# step_motor.net
KiCad netlist of a schematic drawn in EAGLE
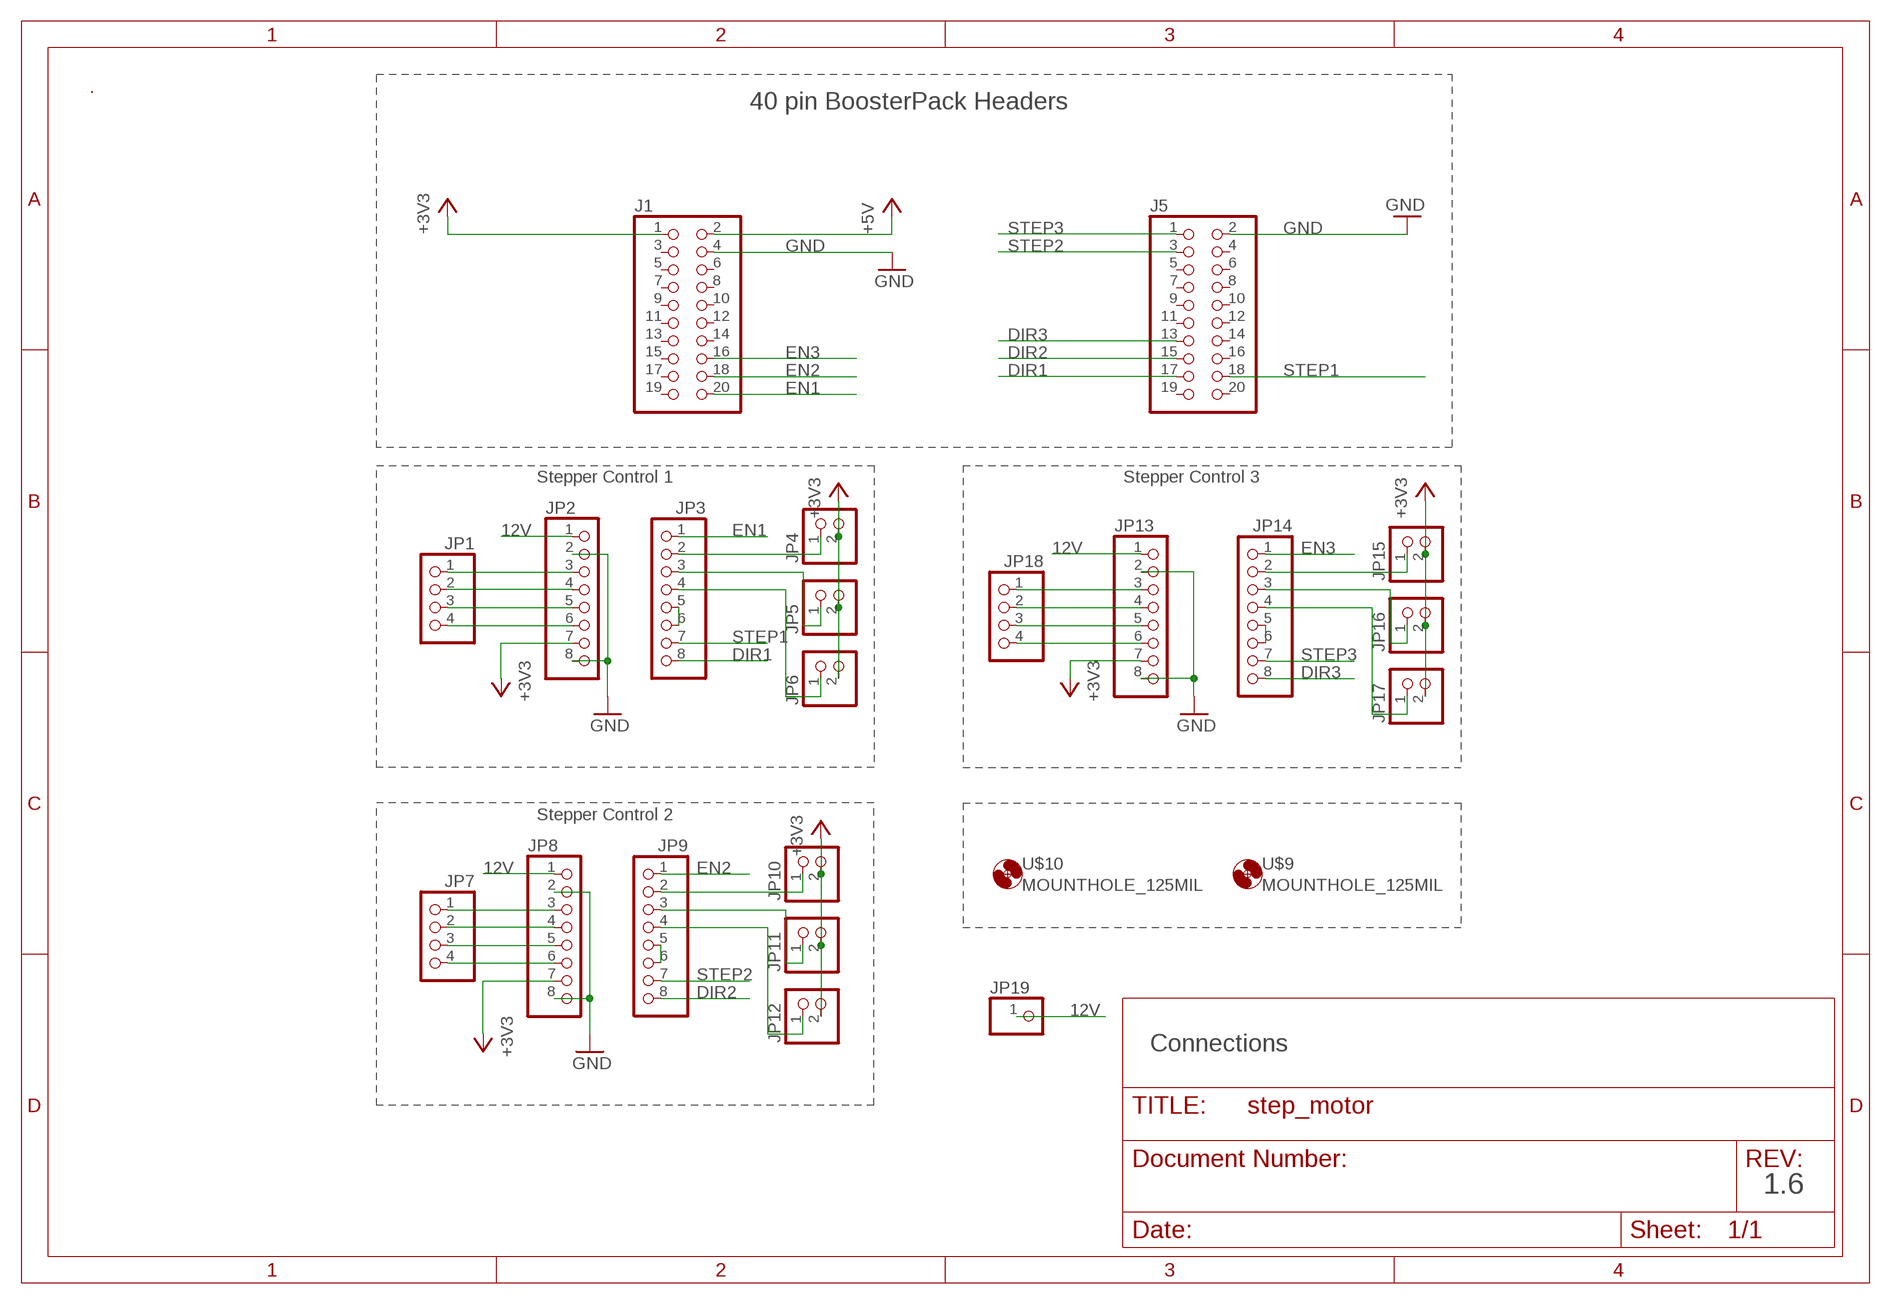
[diagram p0: schematic, sheet 1]

(export (version "E")
  (design (tool "Eeschema 10.0.6"))
  (components
    (comp (ref "J1")
      (value "PINHD-2X10")
      (footprint "eagle-import:2X10")
      (libsource (lib "eagle-import") (part "PINHD-2X10"))
    )
    (comp (ref "J5")
      (value "PINHD-2X10")
      (footprint "eagle-import:2X10")
      (libsource (lib "eagle-import") (part "PINHD-2X10"))
    )
    (comp (ref "JP1")
      (value "PINHD-1X4")
      (footprint "eagle-import:1X04")
      (libsource (lib "eagle-import") (part "PINHD-1X4"))
    )
    (comp (ref "JP2")
      (value "PINHD-1X8")
      (footprint "eagle-import:1X08")
      (libsource (lib "eagle-import") (part "PINHD-1X8"))
    )
    (comp (ref "JP3")
      (value "PINHD-1X8")
      (footprint "eagle-import:1X08")
      (libsource (lib "eagle-import") (part "PINHD-1X8"))
    )
    (comp (ref "JP4")
      (value "PINHD-1X2")
      (footprint "eagle-import:1X02")
      (libsource (lib "eagle-import") (part "PINHD-1X2"))
    )
    (comp (ref "JP5")
      (value "PINHD-1X2")
      (footprint "eagle-import:1X02")
      (libsource (lib "eagle-import") (part "PINHD-1X2"))
    )
    (comp (ref "JP6")
      (value "PINHD-1X2")
      (footprint "eagle-import:1X02")
      (libsource (lib "eagle-import") (part "PINHD-1X2"))
    )
    (comp (ref "JP7")
      (value "PINHD-1X4")
      (footprint "eagle-import:1X04")
      (libsource (lib "eagle-import") (part "PINHD-1X4"))
    )
    (comp (ref "JP8")
      (value "PINHD-1X8")
      (footprint "eagle-import:1X08")
      (libsource (lib "eagle-import") (part "PINHD-1X8"))
    )
    (comp (ref "JP9")
      (value "PINHD-1X8")
      (footprint "eagle-import:1X08")
      (libsource (lib "eagle-import") (part "PINHD-1X8"))
    )
    (comp (ref "JP10")
      (value "PINHD-1X2")
      (footprint "eagle-import:1X02")
      (libsource (lib "eagle-import") (part "PINHD-1X2"))
    )
    (comp (ref "JP11")
      (value "PINHD-1X2")
      (footprint "eagle-import:1X02")
      (libsource (lib "eagle-import") (part "PINHD-1X2"))
    )
    (comp (ref "JP12")
      (value "PINHD-1X2")
      (footprint "eagle-import:1X02")
      (libsource (lib "eagle-import") (part "PINHD-1X2"))
    )
    (comp (ref "JP13")
      (value "PINHD-1X8")
      (footprint "eagle-import:1X08")
      (libsource (lib "eagle-import") (part "PINHD-1X8"))
    )
    (comp (ref "JP14")
      (value "PINHD-1X8")
      (footprint "eagle-import:1X08")
      (libsource (lib "eagle-import") (part "PINHD-1X8"))
    )
    (comp (ref "JP15")
      (value "PINHD-1X2")
      (footprint "eagle-import:1X02")
      (libsource (lib "eagle-import") (part "PINHD-1X2"))
    )
    (comp (ref "JP16")
      (value "PINHD-1X2")
      (footprint "eagle-import:1X02")
      (libsource (lib "eagle-import") (part "PINHD-1X2"))
    )
    (comp (ref "JP17")
      (value "PINHD-1X2")
      (footprint "eagle-import:1X02")
      (libsource (lib "eagle-import") (part "PINHD-1X2"))
    )
    (comp (ref "JP18")
      (value "PINHD-1X4")
      (footprint "eagle-import:1X04")
      (libsource (lib "eagle-import") (part "PINHD-1X4"))
    )
    (comp (ref "JP19")
      (value "PINHD-1X1")
      (footprint "eagle-import:1X01")
      (libsource (lib "eagle-import") (part "PINHD-1X1"))
    )
    (comp (ref "U$4")
      (value "MS_TM")
      (footprint "eagle-import:MS_TM")
      (libsource (lib "eagle-import") (part "MS_TM"))
    )
    (comp (ref "U$9")
      (value "MOUNTHOLE_125MIL")
      (footprint "eagle-import:MOUNTHOLE_125MIL")
      (libsource (lib "eagle-import") (part "MOUNTHOLE_125MIL"))
    )
    (comp (ref "U$10")
      (value "MOUNTHOLE_125MIL")
      (footprint "eagle-import:MOUNTHOLE_125MIL")
      (libsource (lib "eagle-import") (part "MOUNTHOLE_125MIL"))
    )
  )
  (nets
    (net (code "1") (name "+3V3") (class "Default")
      (node (ref "J1") (pin "1") (pinfunction "1_1") (pintype "passive"))
      (node (ref "JP10") (pin "2") (pinfunction "2_2") (pintype "passive"))
      (node (ref "JP11") (pin "2") (pinfunction "2_2") (pintype "passive"))
      (node (ref "JP12") (pin "2") (pinfunction "2_2") (pintype "passive"))
      (node (ref "JP13") (pin "7") (pinfunction "7_7") (pintype "passive"))
      (node (ref "JP15") (pin "2") (pinfunction "2_2") (pintype "passive"))
      (node (ref "JP16") (pin "2") (pinfunction "2_2") (pintype "passive"))
      (node (ref "JP17") (pin "2") (pinfunction "2_2") (pintype "passive"))
      (node (ref "JP2") (pin "7") (pinfunction "7_7") (pintype "passive"))
      (node (ref "JP4") (pin "2") (pinfunction "2_2") (pintype "passive"))
      (node (ref "JP5") (pin "2") (pinfunction "2_2") (pintype "passive"))
      (node (ref "JP6") (pin "2") (pinfunction "2_2") (pintype "passive"))
      (node (ref "JP8") (pin "7") (pinfunction "7_7") (pintype "passive"))
    )
    (net (code "2") (name "+5V") (class "Default")
      (node (ref "J1") (pin "2") (pinfunction "2_2") (pintype "passive"))
    )
    (net (code "3") (name "/12V") (class "Default")
      (node (ref "JP13") (pin "1") (pinfunction "1_1") (pintype "passive"))
      (node (ref "JP19") (pin "1") (pinfunction "1_1") (pintype "passive"))
      (node (ref "JP2") (pin "1") (pinfunction "1_1") (pintype "passive"))
      (node (ref "JP8") (pin "1") (pinfunction "1_1") (pintype "passive"))
    )
    (net (code "4") (name "/DIR1") (class "Default")
      (node (ref "J5") (pin "17") (pinfunction "17_17") (pintype "passive"))
      (node (ref "JP3") (pin "8") (pinfunction "8_8") (pintype "passive"))
    )
    (net (code "5") (name "/DIR2") (class "Default")
      (node (ref "J5") (pin "15") (pinfunction "15_15") (pintype "passive"))
      (node (ref "JP9") (pin "8") (pinfunction "8_8") (pintype "passive"))
    )
    (net (code "6") (name "/DIR3") (class "Default")
      (node (ref "J5") (pin "13") (pinfunction "13_13") (pintype "passive"))
      (node (ref "JP14") (pin "8") (pinfunction "8_8") (pintype "passive"))
    )
    (net (code "7") (name "/EN1") (class "Default")
      (node (ref "J1") (pin "20") (pinfunction "20_20") (pintype "passive"))
      (node (ref "JP3") (pin "1") (pinfunction "1_1") (pintype "passive"))
    )
    (net (code "8") (name "/EN2") (class "Default")
      (node (ref "J1") (pin "18") (pinfunction "18_18") (pintype "passive"))
      (node (ref "JP9") (pin "1") (pinfunction "1_1") (pintype "passive"))
    )
    (net (code "9") (name "/EN3") (class "Default")
      (node (ref "J1") (pin "16") (pinfunction "16_16") (pintype "passive"))
      (node (ref "JP14") (pin "1") (pinfunction "1_1") (pintype "passive"))
    )
    (net (code "10") (name "/STEP1") (class "Default")
      (node (ref "J5") (pin "18") (pinfunction "18_18") (pintype "passive"))
      (node (ref "JP3") (pin "7") (pinfunction "7_7") (pintype "passive"))
    )
    (net (code "11") (name "/STEP2") (class "Default")
      (node (ref "J5") (pin "3") (pinfunction "3_3") (pintype "passive"))
      (node (ref "JP9") (pin "7") (pinfunction "7_7") (pintype "passive"))
    )
    (net (code "12") (name "/STEP3") (class "Default")
      (node (ref "J5") (pin "1") (pinfunction "1_1") (pintype "passive"))
      (node (ref "JP14") (pin "7") (pinfunction "7_7") (pintype "passive"))
    )
    (net (code "13") (name "GND") (class "Default")
      (node (ref "J1") (pin "4") (pinfunction "4_4") (pintype "passive"))
      (node (ref "J5") (pin "2") (pinfunction "2_2") (pintype "passive"))
      (node (ref "JP13") (pin "2") (pinfunction "2_2") (pintype "passive"))
      (node (ref "JP13") (pin "8") (pinfunction "8_8") (pintype "passive"))
      (node (ref "JP2") (pin "2") (pinfunction "2_2") (pintype "passive"))
      (node (ref "JP2") (pin "8") (pinfunction "8_8") (pintype "passive"))
      (node (ref "JP8") (pin "2") (pinfunction "2_2") (pintype "passive"))
      (node (ref "JP8") (pin "8") (pinfunction "8_8") (pintype "passive"))
    )
    (net (code "14") (name "Net-(JP1-Pad1)") (class "Default")
      (node (ref "JP1") (pin "1") (pinfunction "1_1") (pintype "passive"))
      (node (ref "JP2") (pin "3") (pinfunction "3_3") (pintype "passive"))
    )
    (net (code "15") (name "Net-(JP1-Pad2)") (class "Default")
      (node (ref "JP1") (pin "2") (pinfunction "2_2") (pintype "passive"))
      (node (ref "JP2") (pin "4") (pinfunction "4_4") (pintype "passive"))
    )
    (net (code "16") (name "Net-(JP1-Pad3)") (class "Default")
      (node (ref "JP1") (pin "3") (pinfunction "3_3") (pintype "passive"))
      (node (ref "JP2") (pin "5") (pinfunction "5_5") (pintype "passive"))
    )
    (net (code "17") (name "Net-(JP1-Pad4)") (class "Default")
      (node (ref "JP1") (pin "4") (pinfunction "4_4") (pintype "passive"))
      (node (ref "JP2") (pin "6") (pinfunction "6_6") (pintype "passive"))
    )
    (net (code "18") (name "Net-(JP3-Pad2)") (class "Default")
      (node (ref "JP3") (pin "2") (pinfunction "2_2") (pintype "passive"))
      (node (ref "JP4") (pin "1") (pinfunction "1_1") (pintype "passive"))
    )
    (net (code "19") (name "Net-(JP3-Pad3)") (class "Default")
      (node (ref "JP3") (pin "3") (pinfunction "3_3") (pintype "passive"))
      (node (ref "JP5") (pin "1") (pinfunction "1_1") (pintype "passive"))
    )
    (net (code "20") (name "Net-(JP3-Pad4)") (class "Default")
      (node (ref "JP3") (pin "4") (pinfunction "4_4") (pintype "passive"))
      (node (ref "JP6") (pin "1") (pinfunction "1_1") (pintype "passive"))
    )
    (net (code "21") (name "Net-(JP3-Pad5)") (class "Default")
      (node (ref "JP3") (pin "5") (pinfunction "5_5") (pintype "passive"))
      (node (ref "JP3") (pin "6") (pinfunction "6_6") (pintype "passive"))
    )
    (net (code "22") (name "Net-(JP7-Pad1)") (class "Default")
      (node (ref "JP7") (pin "1") (pinfunction "1_1") (pintype "passive"))
      (node (ref "JP8") (pin "3") (pinfunction "3_3") (pintype "passive"))
    )
    (net (code "23") (name "Net-(JP7-Pad2)") (class "Default")
      (node (ref "JP7") (pin "2") (pinfunction "2_2") (pintype "passive"))
      (node (ref "JP8") (pin "4") (pinfunction "4_4") (pintype "passive"))
    )
    (net (code "24") (name "Net-(JP7-Pad3)") (class "Default")
      (node (ref "JP7") (pin "3") (pinfunction "3_3") (pintype "passive"))
      (node (ref "JP8") (pin "5") (pinfunction "5_5") (pintype "passive"))
    )
    (net (code "25") (name "Net-(JP7-Pad4)") (class "Default")
      (node (ref "JP7") (pin "4") (pinfunction "4_4") (pintype "passive"))
      (node (ref "JP8") (pin "6") (pinfunction "6_6") (pintype "passive"))
    )
    (net (code "26") (name "Net-(JP9-Pad5)") (class "Default")
      (node (ref "JP9") (pin "5") (pinfunction "5_5") (pintype "passive"))
      (node (ref "JP9") (pin "6") (pinfunction "6_6") (pintype "passive"))
    )
    (net (code "27") (name "Net-(JP10-Pad1)") (class "Default")
      (node (ref "JP10") (pin "1") (pinfunction "1_1") (pintype "passive"))
      (node (ref "JP9") (pin "2") (pinfunction "2_2") (pintype "passive"))
    )
    (net (code "28") (name "Net-(JP11-Pad1)") (class "Default")
      (node (ref "JP11") (pin "1") (pinfunction "1_1") (pintype "passive"))
      (node (ref "JP9") (pin "3") (pinfunction "3_3") (pintype "passive"))
    )
    (net (code "29") (name "Net-(JP12-Pad1)") (class "Default")
      (node (ref "JP12") (pin "1") (pinfunction "1_1") (pintype "passive"))
      (node (ref "JP9") (pin "4") (pinfunction "4_4") (pintype "passive"))
    )
    (net (code "30") (name "Net-(JP13-Pad3)") (class "Default")
      (node (ref "JP13") (pin "3") (pinfunction "3_3") (pintype "passive"))
      (node (ref "JP18") (pin "1") (pinfunction "1_1") (pintype "passive"))
    )
    (net (code "31") (name "Net-(JP13-Pad4)") (class "Default")
      (node (ref "JP13") (pin "4") (pinfunction "4_4") (pintype "passive"))
      (node (ref "JP18") (pin "2") (pinfunction "2_2") (pintype "passive"))
    )
    (net (code "32") (name "Net-(JP13-Pad5)") (class "Default")
      (node (ref "JP13") (pin "5") (pinfunction "5_5") (pintype "passive"))
      (node (ref "JP18") (pin "3") (pinfunction "3_3") (pintype "passive"))
    )
    (net (code "33") (name "Net-(JP13-Pad6)") (class "Default")
      (node (ref "JP13") (pin "6") (pinfunction "6_6") (pintype "passive"))
      (node (ref "JP18") (pin "4") (pinfunction "4_4") (pintype "passive"))
    )
    (net (code "34") (name "Net-(JP14-Pad2)") (class "Default")
      (node (ref "JP14") (pin "2") (pinfunction "2_2") (pintype "passive"))
      (node (ref "JP15") (pin "1") (pinfunction "1_1") (pintype "passive"))
    )
    (net (code "35") (name "Net-(JP14-Pad3)") (class "Default")
      (node (ref "JP14") (pin "3") (pinfunction "3_3") (pintype "passive"))
      (node (ref "JP16") (pin "1") (pinfunction "1_1") (pintype "passive"))
    )
    (net (code "36") (name "Net-(JP14-Pad4)") (class "Default")
      (node (ref "JP14") (pin "4") (pinfunction "4_4") (pintype "passive"))
      (node (ref "JP17") (pin "1") (pinfunction "1_1") (pintype "passive"))
    )
    (net (code "37") (name "Net-(JP14-Pad5)") (class "Default")
      (node (ref "JP14") (pin "5") (pinfunction "5_5") (pintype "passive"))
      (node (ref "JP14") (pin "6") (pinfunction "6_6") (pintype "passive"))
    )
    (net (code "38") (name "unconnected-(J1-Pad3)") (class "Default")
      (node (ref "J1") (pin "3") (pinfunction "3_3") (pintype "passive"))
    )
    (net (code "39") (name "unconnected-(J1-Pad5)") (class "Default")
      (node (ref "J1") (pin "5") (pinfunction "5_5") (pintype "passive"))
    )
    (net (code "40") (name "unconnected-(J1-Pad6)") (class "Default")
      (node (ref "J1") (pin "6") (pinfunction "6_6") (pintype "passive"))
    )
    (net (code "41") (name "unconnected-(J1-Pad7)") (class "Default")
      (node (ref "J1") (pin "7") (pinfunction "7_7") (pintype "passive"))
    )
    (net (code "42") (name "unconnected-(J1-Pad8)") (class "Default")
      (node (ref "J1") (pin "8") (pinfunction "8_8") (pintype "passive"))
    )
    (net (code "43") (name "unconnected-(J1-Pad9)") (class "Default")
      (node (ref "J1") (pin "9") (pinfunction "9_9") (pintype "passive"))
    )
    (net (code "44") (name "unconnected-(J1-Pad10)") (class "Default")
      (node (ref "J1") (pin "10") (pinfunction "10_10") (pintype "passive"))
    )
    (net (code "45") (name "unconnected-(J1-Pad11)") (class "Default")
      (node (ref "J1") (pin "11") (pinfunction "11_11") (pintype "passive"))
    )
    (net (code "46") (name "unconnected-(J1-Pad12)") (class "Default")
      (node (ref "J1") (pin "12") (pinfunction "12_12") (pintype "passive"))
    )
    (net (code "47") (name "unconnected-(J1-Pad13)") (class "Default")
      (node (ref "J1") (pin "13") (pinfunction "13_13") (pintype "passive"))
    )
    (net (code "48") (name "unconnected-(J1-Pad14)") (class "Default")
      (node (ref "J1") (pin "14") (pinfunction "14_14") (pintype "passive"))
    )
    (net (code "49") (name "unconnected-(J1-Pad15)") (class "Default")
      (node (ref "J1") (pin "15") (pinfunction "15_15") (pintype "passive"))
    )
    (net (code "50") (name "unconnected-(J1-Pad17)") (class "Default")
      (node (ref "J1") (pin "17") (pinfunction "17_17") (pintype "passive"))
    )
    (net (code "51") (name "unconnected-(J1-Pad19)") (class "Default")
      (node (ref "J1") (pin "19") (pinfunction "19_19") (pintype "passive"))
    )
    (net (code "52") (name "unconnected-(J5-Pad4)") (class "Default")
      (node (ref "J5") (pin "4") (pinfunction "4_4") (pintype "passive"))
    )
    (net (code "53") (name "unconnected-(J5-Pad5)") (class "Default")
      (node (ref "J5") (pin "5") (pinfunction "5_5") (pintype "passive"))
    )
    (net (code "54") (name "unconnected-(J5-Pad6)") (class "Default")
      (node (ref "J5") (pin "6") (pinfunction "6_6") (pintype "passive"))
    )
    (net (code "55") (name "unconnected-(J5-Pad7)") (class "Default")
      (node (ref "J5") (pin "7") (pinfunction "7_7") (pintype "passive"))
    )
    (net (code "56") (name "unconnected-(J5-Pad8)") (class "Default")
      (node (ref "J5") (pin "8") (pinfunction "8_8") (pintype "passive"))
    )
    (net (code "57") (name "unconnected-(J5-Pad9)") (class "Default")
      (node (ref "J5") (pin "9") (pinfunction "9_9") (pintype "passive"))
    )
    (net (code "58") (name "unconnected-(J5-Pad10)") (class "Default")
      (node (ref "J5") (pin "10") (pinfunction "10_10") (pintype "passive"))
    )
    (net (code "59") (name "unconnected-(J5-Pad11)") (class "Default")
      (node (ref "J5") (pin "11") (pinfunction "11_11") (pintype "passive"))
    )
    (net (code "60") (name "unconnected-(J5-Pad12)") (class "Default")
      (node (ref "J5") (pin "12") (pinfunction "12_12") (pintype "passive"))
    )
    (net (code "61") (name "unconnected-(J5-Pad14)") (class "Default")
      (node (ref "J5") (pin "14") (pinfunction "14_14") (pintype "passive"))
    )
    (net (code "62") (name "unconnected-(J5-Pad16)") (class "Default")
      (node (ref "J5") (pin "16") (pinfunction "16_16") (pintype "passive"))
    )
    (net (code "63") (name "unconnected-(J5-Pad19)") (class "Default")
      (node (ref "J5") (pin "19") (pinfunction "19_19") (pintype "passive"))
    )
    (net (code "64") (name "unconnected-(J5-Pad20)") (class "Default")
      (node (ref "J5") (pin "20") (pinfunction "20_20") (pintype "passive"))
    )
  )
)
